# 1-Schematic_SAE301.net
KiCad netlist of a schematic drawn in EasyEDA
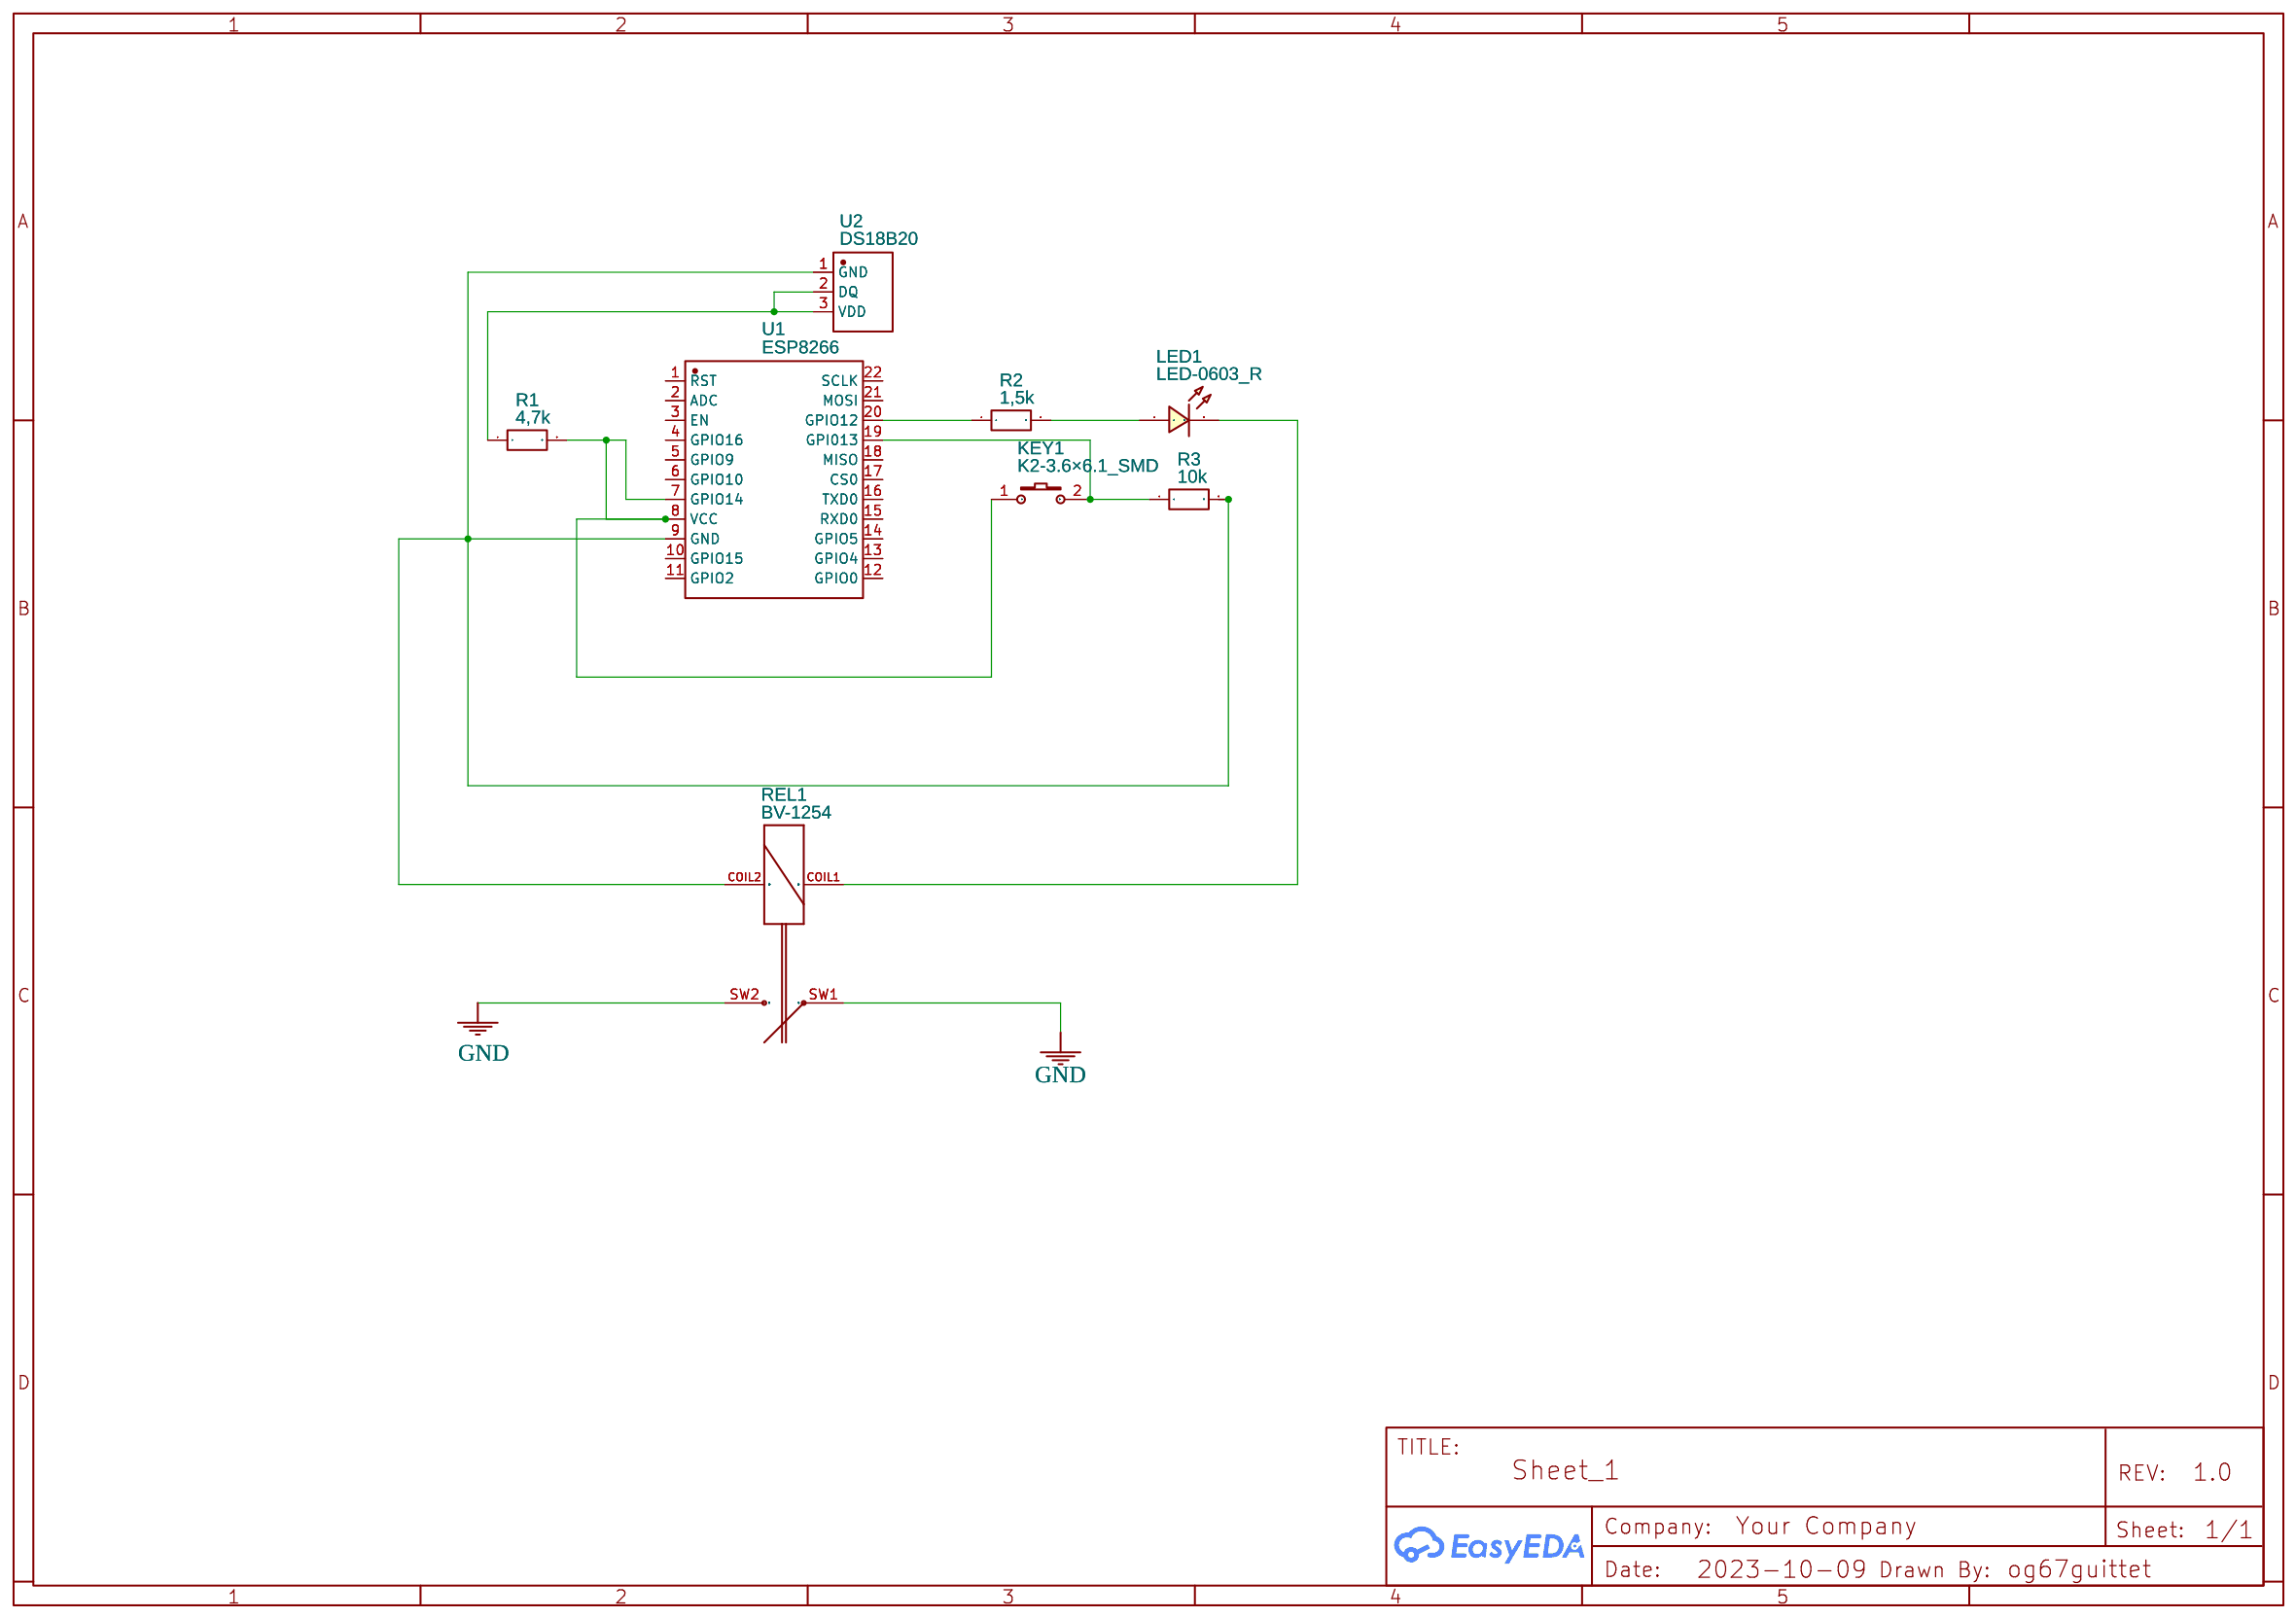
[diagram p0: schematic sheet]

(export (version "E")
  (design (tool "Eeschema 10.0.6"))
  (components
    (comp (ref "KEY1")
      (value "K2-3.6×6.1_SMD")
      (fields (field (name "Manufacturer Part") "K2-1107ST-A4SW-06"))
      (libsource (lib "") (part "K2-3.6×6.1_SMD"))
    )
    (comp (ref "LED1")
      (value "LED-0603_R")
      (fields
        (field (name "Manufacturer Part") "19-217/R6C-AL1M2VY/3T")
        (field (name "Manufacturer") "EVERLIGHT(台湾亿光)")
      )
      (libsource (lib "") (part "LED-0603_R"))
    )
    (comp (ref "R1") (value "4,7k") (libsource (lib "") (part "R_0603_EU")))
    (comp (ref "R2") (value "1,5k") (libsource (lib "") (part "R_0603_EU")))
    (comp (ref "R3") (value "10k") (libsource (lib "") (part "R_0603_EU")))
    (comp (ref "REL1") (value "BV-1254") (libsource (lib "") (part "BV-1254")))
    (comp (ref "U1") (value "ESP8266") (libsource (lib "") (part "ESP8266")))
    (comp (ref "U2")
      (value "DS18B20")
      (fields (field (name "Manufacturer") "UMW(广东友台半导体)"))
      (libsource (lib "") (part "DS18B20"))
    )
  )
  (nets
    (net (code "1") (name "GND") (class "Default")
      (node (ref "REL1") (pin "SW1") (pinfunction "SW1_SW1") (pintype "unspecified"))
      (node (ref "REL1") (pin "SW2") (pinfunction "SW2_SW2") (pintype "unspecified"))
    )
    (net (code "2") (name "Net-(LED1-Pad1)") (class "Default")
      (node (ref "LED1") (pin "1") (pinfunction "1_1") (pintype "unspecified"))
      (node (ref "R2") (pin "2") (pinfunction "2_2") (pintype "unspecified"))
    )
    (net (code "3") (name "Net-(LED1-Pad2)") (class "Default")
      (node (ref "LED1") (pin "2") (pinfunction "2_2") (pintype "unspecified"))
      (node (ref "REL1") (pin "COIL1") (pinfunction "COIL1_COIL1") (pintype "input"))
    )
    (net (code "4") (name "Net-(U1-GND)") (class "Default")
      (node (ref "R3") (pin "2") (pinfunction "2_2") (pintype "unspecified"))
      (node (ref "REL1") (pin "COIL2") (pinfunction "COIL2_COIL2") (pintype "input"))
      (node (ref "U1") (pin "9") (pinfunction "GND_9") (pintype "unspecified"))
      (node (ref "U2") (pin "1") (pinfunction "GND_1") (pintype "unspecified"))
    )
    (net (code "5") (name "Net-(U1-GPI013)") (class "Default")
      (node (ref "KEY1") (pin "2") (pinfunction "2_2") (pintype "unspecified"))
      (node (ref "R3") (pin "1") (pinfunction "1_1") (pintype "unspecified"))
      (node (ref "U1") (pin "19") (pinfunction "GPI013_19") (pintype "unspecified"))
    )
    (net (code "6") (name "Net-(U1-GPIO12)") (class "Default")
      (node (ref "R2") (pin "1") (pinfunction "1_1") (pintype "unspecified"))
      (node (ref "U1") (pin "20") (pinfunction "GPIO12_20") (pintype "unspecified"))
    )
    (net (code "7") (name "Net-(U1-GPIO14)") (class "Default")
      (node (ref "KEY1") (pin "1") (pinfunction "1_1") (pintype "unspecified"))
      (node (ref "R1") (pin "2") (pinfunction "2_2") (pintype "unspecified"))
      (node (ref "U1") (pin "7") (pinfunction "GPIO14_7") (pintype "unspecified"))
      (node (ref "U1") (pin "8") (pinfunction "VCC_8") (pintype "unspecified"))
    )
    (net (code "8") (name "Net-(U2-DQ)") (class "Default")
      (node (ref "R1") (pin "1") (pinfunction "1_1") (pintype "unspecified"))
      (node (ref "U2") (pin "2") (pinfunction "DQ_2") (pintype "unspecified"))
      (node (ref "U2") (pin "3") (pinfunction "VDD_3") (pintype "unspecified"))
    )
    (net (code "9") (name "unconnected-(U1-ADC-Pad2)") (class "Default")
      (node (ref "U1") (pin "2") (pinfunction "ADC_2") (pintype "unspecified"))
    )
    (net (code "10") (name "unconnected-(U1-CS0-Pad17)") (class "Default")
      (node (ref "U1") (pin "17") (pinfunction "CS0_17") (pintype "unspecified"))
    )
    (net (code "11") (name "unconnected-(U1-EN-Pad3)") (class "Default")
      (node (ref "U1") (pin "3") (pinfunction "EN_3") (pintype "unspecified"))
    )
    (net (code "12") (name "unconnected-(U1-GPIO0-Pad12)") (class "Default")
      (node (ref "U1") (pin "12") (pinfunction "GPIO0_12") (pintype "unspecified"))
    )
    (net (code "13") (name "unconnected-(U1-GPIO2-Pad11)") (class "Default")
      (node (ref "U1") (pin "11") (pinfunction "GPIO2_11") (pintype "unspecified"))
    )
    (net (code "14") (name "unconnected-(U1-GPIO4-Pad13)") (class "Default")
      (node (ref "U1") (pin "13") (pinfunction "GPIO4_13") (pintype "unspecified"))
    )
    (net (code "15") (name "unconnected-(U1-GPIO5-Pad14)") (class "Default")
      (node (ref "U1") (pin "14") (pinfunction "GPIO5_14") (pintype "unspecified"))
    )
    (net (code "16") (name "unconnected-(U1-GPIO9-Pad5)") (class "Default")
      (node (ref "U1") (pin "5") (pinfunction "GPIO9_5") (pintype "unspecified"))
    )
    (net (code "17") (name "unconnected-(U1-GPIO10-Pad6)") (class "Default")
      (node (ref "U1") (pin "6") (pinfunction "GPIO10_6") (pintype "unspecified"))
    )
    (net (code "18") (name "unconnected-(U1-GPIO15-Pad10)") (class "Default")
      (node (ref "U1") (pin "10") (pinfunction "GPIO15_10") (pintype "unspecified"))
    )
    (net (code "19") (name "unconnected-(U1-GPIO16-Pad4)") (class "Default")
      (node (ref "U1") (pin "4") (pinfunction "GPIO16_4") (pintype "unspecified"))
    )
    (net (code "20") (name "unconnected-(U1-MISO-Pad18)") (class "Default")
      (node (ref "U1") (pin "18") (pinfunction "MISO_18") (pintype "unspecified"))
    )
    (net (code "21") (name "unconnected-(U1-MOSI-Pad21)") (class "Default")
      (node (ref "U1") (pin "21") (pinfunction "MOSI_21") (pintype "unspecified"))
    )
    (net (code "22") (name "unconnected-(U1-RST-Pad1)") (class "Default")
      (node (ref "U1") (pin "1") (pinfunction "RST_1") (pintype "unspecified"))
    )
    (net (code "23") (name "unconnected-(U1-RXD0-Pad15)") (class "Default")
      (node (ref "U1") (pin "15") (pinfunction "RXD0_15") (pintype "unspecified"))
    )
    (net (code "24") (name "unconnected-(U1-SCLK-Pad22)") (class "Default")
      (node (ref "U1") (pin "22") (pinfunction "SCLK_22") (pintype "unspecified"))
    )
    (net (code "25") (name "unconnected-(U1-TXD0-Pad16)") (class "Default")
      (node (ref "U1") (pin "16") (pinfunction "TXD0_16") (pintype "unspecified"))
    )
  )
)
